# Sheet1.net
KiCad netlist of a schematic drawn in Altium Designer
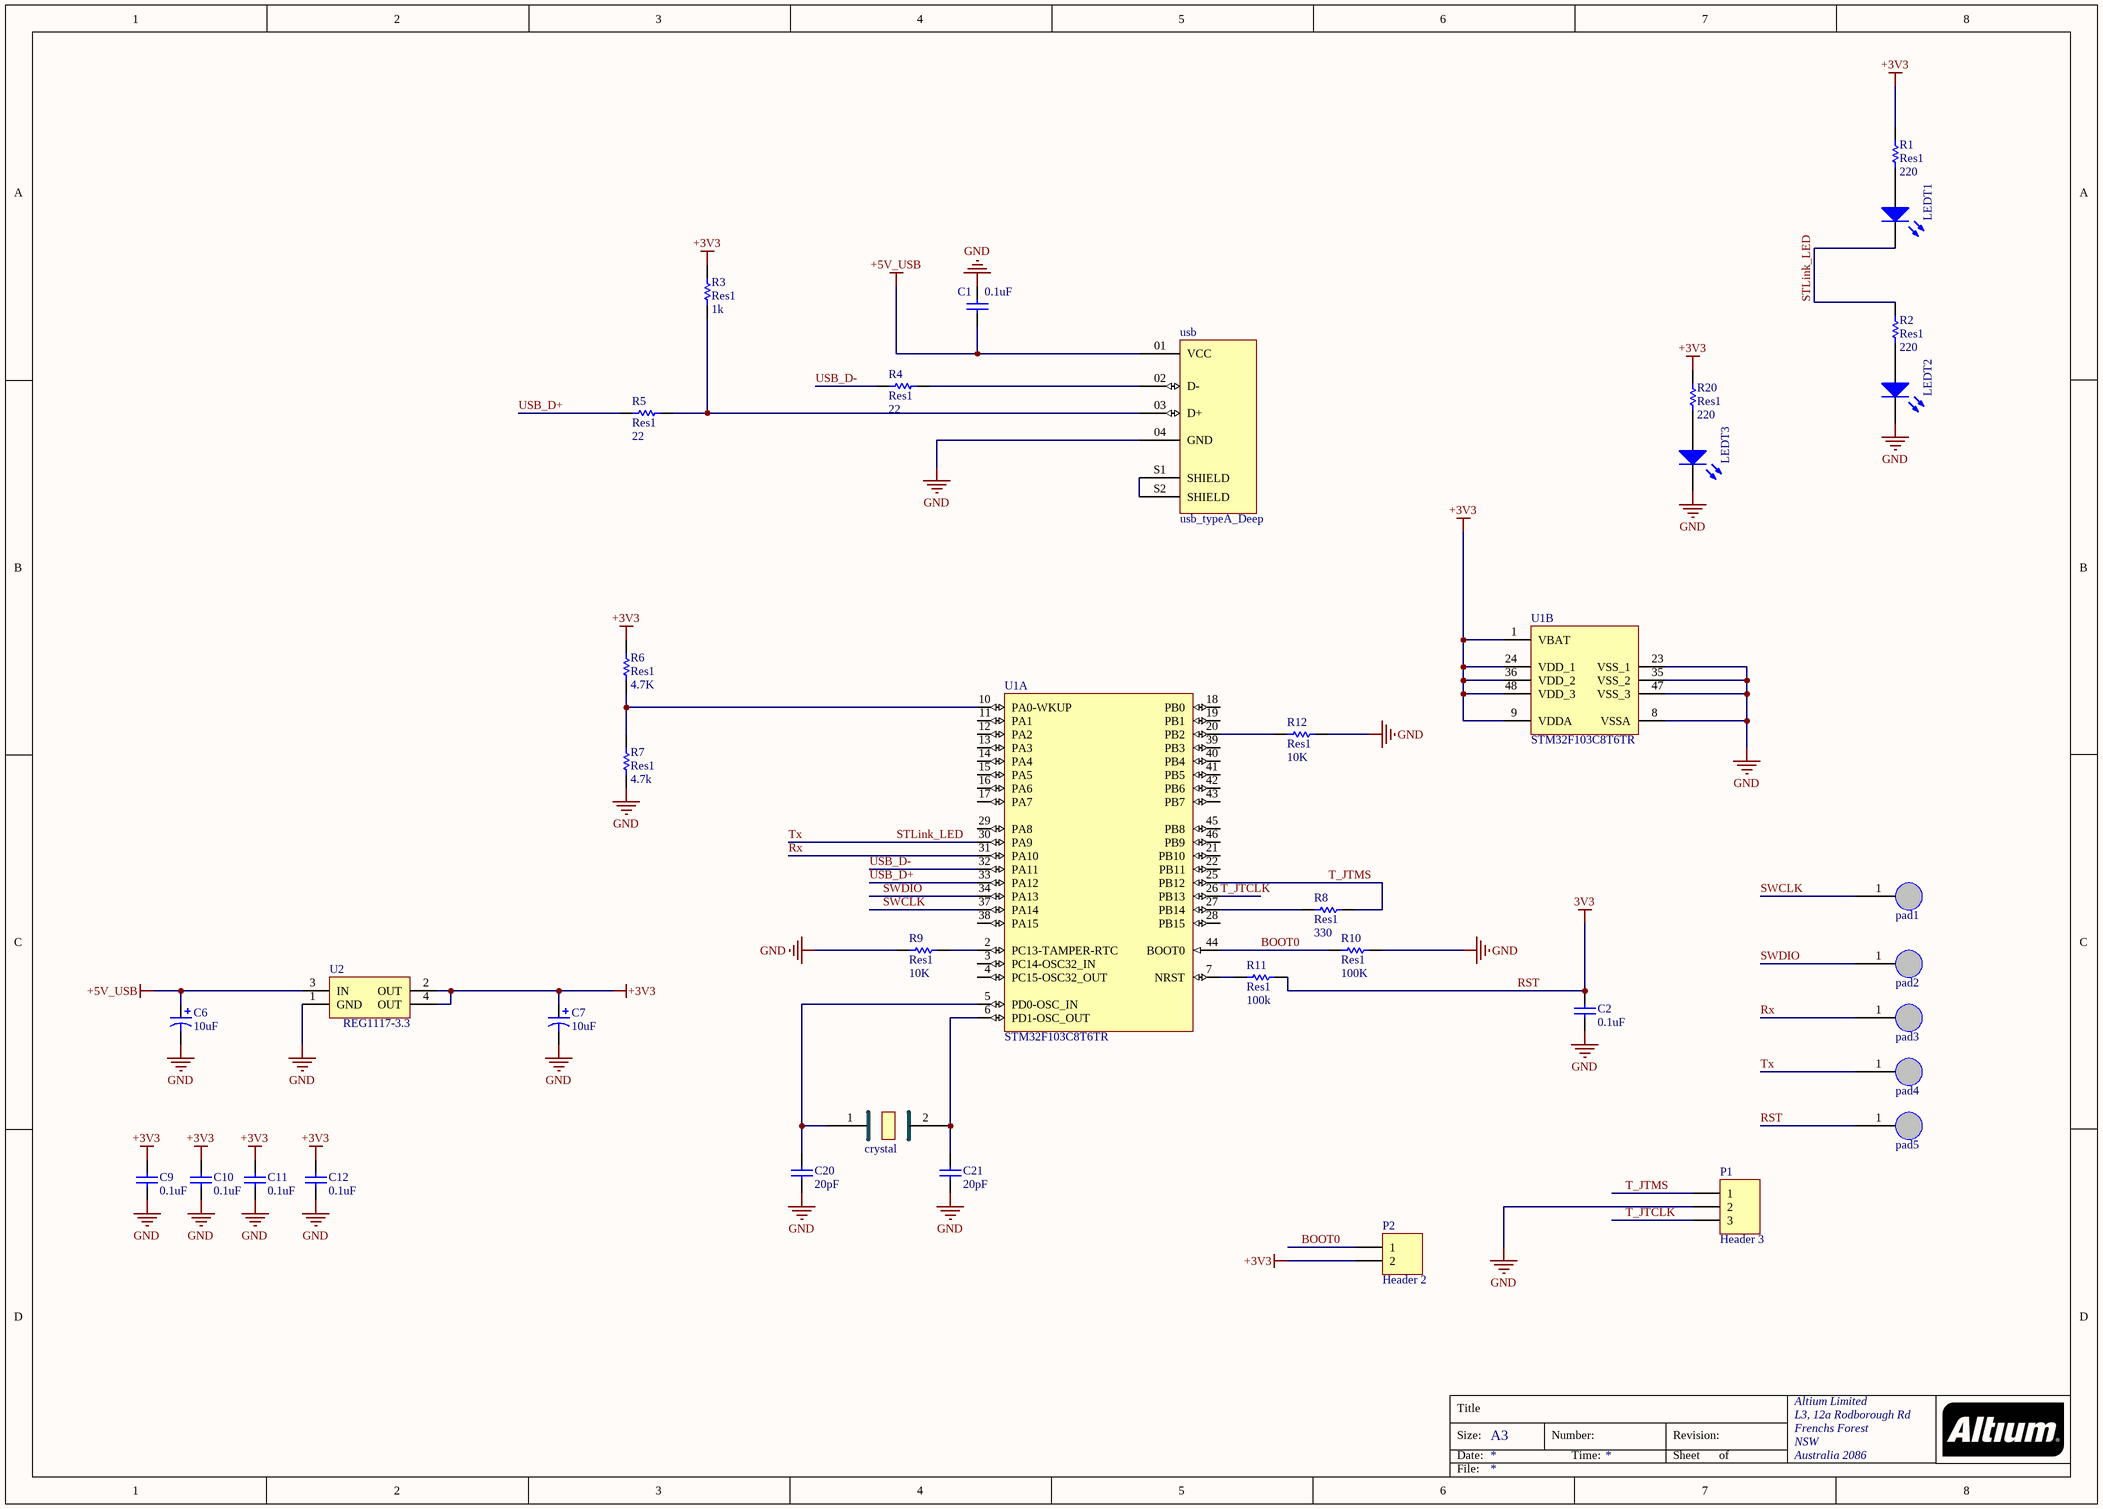
[diagram p0: Sheet1.SchDoc]

(export (version "E")
  (design (tool "Eeschema 10.0.6"))
  (components
    (comp (ref "C1")
      (value "0.1uF")
      (footprint "J1-0603")
      (description "Ceramic Chip Capacitor - Standard")
      (fields (field (name "Comment") "C0603") (field (name "PUBLISHER") "Altium Limited"))
      (libsource (lib "KEMET Chip Capacitor") (part "C0603"))
    )
    (comp (ref "C2")
      (value "0.1uF")
      (footprint "J1-0603")
      (description "Ceramic Chip Capacitor - Standard")
      (fields (field (name "Comment") "C0603") (field (name "PUBLISHER") "Altium Limited"))
      (libsource (lib "KEMET Chip Capacitor") (part "C0603"))
    )
    (comp (ref "C6")
      (value "10uF")
      (footprint "J1-0603")
      (fields (field (name "PUBLISHER") "Altium Limited"))
      (libsource (lib "Vishay Sprague Tantalum Chip Capacitor") (part "194D105X0015B2"))
    )
    (comp (ref "C7")
      (value "10uF")
      (footprint "J1-0603")
      (fields (field (name "PUBLISHER") "Altium Limited"))
      (libsource (lib "Vishay Sprague Tantalum Chip Capacitor") (part "194D105X0015B2"))
    )
    (comp (ref "C9")
      (value "0.1uF")
      (footprint "J1-0603")
      (description "Ceramic Chip Capacitor - Standard")
      (fields (field (name "Comment") "C0603") (field (name "PUBLISHER") "Altium Limited"))
      (libsource (lib "KEMET Chip Capacitor") (part "C0603"))
    )
    (comp (ref "C10")
      (value "0.1uF")
      (footprint "J1-0603")
      (description "Ceramic Chip Capacitor - Standard")
      (fields (field (name "Comment") "C0603") (field (name "PUBLISHER") "Altium Limited"))
      (libsource (lib "KEMET Chip Capacitor") (part "C0603"))
    )
    (comp (ref "C11")
      (value "0.1uF")
      (footprint "J1-0603")
      (description "Ceramic Chip Capacitor - Standard")
      (fields (field (name "Comment") "C0603") (field (name "PUBLISHER") "Altium Limited"))
      (libsource (lib "KEMET Chip Capacitor") (part "C0603"))
    )
    (comp (ref "C12")
      (value "0.1uF")
      (footprint "J1-0603")
      (description "Ceramic Chip Capacitor - Standard")
      (fields (field (name "Comment") "C0603") (field (name "PUBLISHER") "Altium Limited"))
      (libsource (lib "KEMET Chip Capacitor") (part "C0603"))
    )
    (comp (ref "C20")
      (value "20pF")
      (footprint "J1-0603")
      (description "Ceramic Chip Capacitor - Standard")
      (fields (field (name "Comment") "C0603") (field (name "PUBLISHER") "Altium Limited"))
      (libsource (lib "KEMET Chip Capacitor") (part "C0603"))
    )
    (comp (ref "C21")
      (value "20pF")
      (footprint "J1-0603")
      (description "Ceramic Chip Capacitor - Standard")
      (fields (field (name "Comment") "C0603") (field (name "PUBLISHER") "Altium Limited"))
      (libsource (lib "KEMET Chip Capacitor") (part "C0603"))
    )
    (comp (ref "crystal")
      (value "clockProducerDeep")
      (footprint "deep crystal")
      (libsource (lib "Schlib1") (part "deep crystal"))
    )
    (comp (ref "LEDT1")
      (value "~")
      (footprint "3518")
      (description "Typical BLUE SiC LED")
      (fields (field (name "PUBLISHER") "Altium Limited"))
      (libsource (lib "Miscellaneous Devices") (part "LED3"))
    )
    (comp (ref "LEDT2")
      (value "~")
      (footprint "3518")
      (description "Typical BLUE SiC LED")
      (fields (field (name "PUBLISHER") "Altium Limited"))
      (libsource (lib "Miscellaneous Devices") (part "LED3"))
    )
    (comp (ref "LEDT3")
      (value "~")
      (footprint "3518")
      (description "Typical BLUE SiC LED")
      (fields (field (name "PUBLISHER") "Altium Limited"))
      (libsource (lib "Miscellaneous Devices") (part "LED3"))
    )
    (comp (ref "P1")
      (value "Header 3")
      (footprint "HDR1X3")
      (description "Header, 3-Pin")
      (fields (field (name "PUBLISHER") "Altium Limited"))
      (libsource (lib "Miscellaneous Connectors") (part "Header 3"))
    )
    (comp (ref "P2")
      (value "Header 2")
      (footprint "HDR1X2")
      (description "Header, 2-Pin")
      (fields (field (name "PUBLISHER") "Altium Limited"))
      (libsource (lib "Miscellaneous Connectors") (part "Header 2"))
    )
    (comp (ref "pad1")
      (value "pad")
      (footprint "pad!")
      (description "test pad")
      (libsource (lib "Schlib1") (part "pad!"))
    )
    (comp (ref "pad2")
      (value "pad")
      (footprint "pad!")
      (description "test pad")
      (libsource (lib "Schlib1") (part "pad!"))
    )
    (comp (ref "pad3")
      (value "pad")
      (footprint "pad!")
      (description "test pad")
      (libsource (lib "Schlib1") (part "pad!"))
    )
    (comp (ref "pad4")
      (value "pad")
      (footprint "pad!")
      (description "test pad")
      (libsource (lib "Schlib1") (part "pad!"))
    )
    (comp (ref "pad5")
      (value "pad")
      (footprint "pad!")
      (description "test pad")
      (libsource (lib "Schlib1") (part "pad!"))
    )
    (comp (ref "R1")
      (value "Res1")
      (footprint "j1-0603")
      (description "Resistor")
      (fields (field (name "ALTIUM_VALUE") "220") (field (name "PUBLISHER") "Altium Limited"))
      (libsource (lib "Miscellaneous Devices") (part "Res1"))
    )
    (comp (ref "R2")
      (value "Res1")
      (footprint "j1-0603")
      (description "Resistor")
      (fields (field (name "ALTIUM_VALUE") "220") (field (name "PUBLISHER") "Altium Limited"))
      (libsource (lib "Miscellaneous Devices") (part "Res1"))
    )
    (comp (ref "R3")
      (value "Res1")
      (footprint "J1-0603")
      (description "Resistor")
      (fields (field (name "ALTIUM_VALUE") "1k") (field (name "PUBLISHER") "Altium Limited"))
      (libsource (lib "Miscellaneous Devices") (part "Res1"))
    )
    (comp (ref "R4")
      (value "Res1")
      (footprint "J1-0603")
      (description "Resistor")
      (fields (field (name "ALTIUM_VALUE") "22") (field (name "PUBLISHER") "Altium Limited"))
      (libsource (lib "Miscellaneous Devices") (part "Res1"))
    )
    (comp (ref "R5")
      (value "Res1")
      (footprint "J1-0603")
      (description "Resistor")
      (fields (field (name "ALTIUM_VALUE") "22") (field (name "PUBLISHER") "Altium Limited"))
      (libsource (lib "Miscellaneous Devices") (part "Res1"))
    )
    (comp (ref "R6")
      (value "Res1")
      (footprint "J1-0603")
      (description "Resistor")
      (fields (field (name "ALTIUM_VALUE") "4.7K") (field (name "PUBLISHER") "Altium Limited"))
      (libsource (lib "Miscellaneous Devices") (part "Res1"))
    )
    (comp (ref "R7")
      (value "Res1")
      (footprint "J1-0603")
      (description "Resistor")
      (fields (field (name "ALTIUM_VALUE") "4.7k") (field (name "PUBLISHER") "Altium Limited"))
      (libsource (lib "Miscellaneous Devices") (part "Res1"))
    )
    (comp (ref "R8")
      (value "Res1")
      (footprint "J1-0603")
      (description "Resistor")
      (fields (field (name "ALTIUM_VALUE") "330") (field (name "PUBLISHER") "Altium Limited"))
      (libsource (lib "Miscellaneous Devices") (part "Res1"))
    )
    (comp (ref "R9")
      (value "Res1")
      (footprint "J1-0603")
      (description "Resistor")
      (fields (field (name "ALTIUM_VALUE") "10K") (field (name "PUBLISHER") "Altium Limited"))
      (libsource (lib "Miscellaneous Devices") (part "Res1"))
    )
    (comp (ref "R10")
      (value "Res1")
      (footprint "J1-0603")
      (description "Resistor")
      (fields (field (name "ALTIUM_VALUE") "100K") (field (name "PUBLISHER") "Altium Limited"))
      (libsource (lib "Miscellaneous Devices") (part "Res1"))
    )
    (comp (ref "R11")
      (value "Res1")
      (footprint "J1-0603")
      (description "Resistor")
      (fields (field (name "ALTIUM_VALUE") "100k") (field (name "PUBLISHER") "Altium Limited"))
      (libsource (lib "Miscellaneous Devices") (part "Res1"))
    )
    (comp (ref "R12")
      (value "Res1")
      (footprint "J1-0603")
      (description "Resistor")
      (fields (field (name "ALTIUM_VALUE") "10K") (field (name "PUBLISHER") "Altium Limited"))
      (libsource (lib "Miscellaneous Devices") (part "Res1"))
    )
    (comp (ref "R20")
      (value "Res1")
      (footprint "j1-0603")
      (description "Resistor")
      (fields (field (name "ALTIUM_VALUE") "220") (field (name "PUBLISHER") "Altium Limited"))
      (libsource (lib "Miscellaneous Devices") (part "Res1"))
    )
    (comp (ref "U1")
      (value "STM32F103C8T6TR")
      (footprint "STM-LQFP48_L")
      (libsource (lib "STMicroelectronics STM32 F1") (part "STM32F103C8T6TR"))
    )
    (comp (ref "U2")
      (value "REG1117-3.3")
      (footprint "SOT223")
      (description "800mA and 1A Low Dropout Positive Regulator 2.85V, 3.3V, 5V, and Adjustable")
      (fields (field (name "PUBLISHER") "Altium Limited"))
      (libsource (lib "BB Power Mgt Voltage Regulator") (part "REG1117-3.3"))
    )
    (comp (ref "usb")
      (value "usb_typeA_Deep")
      (footprint "usb_typeA_Deep")
      (libsource (lib "Schlib1") (part "usb_typeA_Deep"))
    )
  )
  (nets
    (net (code "1") (name "+3V3") (class "Default")
      (node (ref "C10") (pin "2") (pinfunction "2_2") (pintype "passive"))
      (node (ref "C11") (pin "2") (pinfunction "2_2") (pintype "passive"))
      (node (ref "C12") (pin "2") (pinfunction "2_2") (pintype "passive"))
      (node (ref "C7") (pin "1") (pinfunction "1_1") (pintype "passive"))
      (node (ref "C9") (pin "2") (pinfunction "2_2") (pintype "passive"))
      (node (ref "P2") (pin "2") (pinfunction "2_2") (pintype "passive"))
      (node (ref "R1") (pin "1") (pinfunction "1_1") (pintype "passive"))
      (node (ref "R20") (pin "1") (pinfunction "1_1") (pintype "passive"))
      (node (ref "R3") (pin "2") (pinfunction "2_2") (pintype "passive"))
      (node (ref "R6") (pin "2") (pinfunction "2_2") (pintype "passive"))
      (node (ref "U1") (pin "1") (pinfunction "VBAT_1") (pintype "power_in"))
      (node (ref "U1") (pin "24") (pinfunction "VDD_1_24") (pintype "power_in"))
      (node (ref "U1") (pin "36") (pinfunction "VDD_2_36") (pintype "power_in"))
      (node (ref "U1") (pin "48") (pinfunction "VDD_3_48") (pintype "power_in"))
      (node (ref "U1") (pin "9") (pinfunction "VDDA_9") (pintype "power_in"))
      (node (ref "U2") (pin "2") (pinfunction "OUT_2") (pintype "power_in"))
      (node (ref "U2") (pin "4") (pinfunction "OUT_4") (pintype "power_in"))
    )
    (net (code "2") (name "+5V_USB") (class "Default")
      (node (ref "C1") (pin "1") (pinfunction "1_1") (pintype "passive"))
      (node (ref "C6") (pin "1") (pinfunction "1_1") (pintype "passive"))
      (node (ref "U2") (pin "3") (pinfunction "IN_3") (pintype "power_in"))
      (node (ref "usb") (pin "01") (pinfunction "VCC_01") (pintype "passive"))
    )
    (net (code "3") (name "/BOOT0") (class "Default")
      (node (ref "P2") (pin "1") (pinfunction "1_1") (pintype "passive"))
      (node (ref "R10") (pin "1") (pinfunction "1_1") (pintype "passive"))
      (node (ref "U1") (pin "44") (pinfunction "BOOT0_44") (pintype "input"))
    )
    (net (code "4") (name "/Rx") (class "Default")
      (node (ref "U1") (pin "31") (pinfunction "PA10_31") (pintype "bidirectional"))
      (node (ref "pad3") (pin "1") (pinfunction "1_1") (pintype "passive"))
    )
    (net (code "5") (name "/STLink_LED") (class "Default")
      (node (ref "LEDT1") (pin "2") (pinfunction "K_2") (pintype "passive"))
      (node (ref "R2") (pin "1") (pinfunction "1_1") (pintype "passive"))
      (node (ref "U1") (pin "30") (pinfunction "PA9_30") (pintype "bidirectional"))
      (node (ref "pad4") (pin "1") (pinfunction "1_1") (pintype "passive"))
    )
    (net (code "6") (name "/SWCLK") (class "Default")
      (node (ref "U1") (pin "37") (pinfunction "PA14_37") (pintype "bidirectional"))
      (node (ref "pad1") (pin "1") (pinfunction "1_1") (pintype "passive"))
    )
    (net (code "7") (name "/SWDIO") (class "Default")
      (node (ref "U1") (pin "34") (pinfunction "PA13_34") (pintype "bidirectional"))
      (node (ref "pad2") (pin "1") (pinfunction "1_1") (pintype "passive"))
    )
    (net (code "8") (name "/T_JTCLK") (class "Default")
      (node (ref "P1") (pin "3") (pinfunction "3_3") (pintype "passive"))
      (node (ref "U1") (pin "26") (pinfunction "PB13_26") (pintype "bidirectional"))
    )
    (net (code "9") (name "/T_JTMS") (class "Default")
      (node (ref "P1") (pin "1") (pinfunction "1_1") (pintype "passive"))
      (node (ref "R8") (pin "2") (pinfunction "2_2") (pintype "passive"))
      (node (ref "U1") (pin "25") (pinfunction "PB12_25") (pintype "bidirectional"))
    )
    (net (code "10") (name "/USB_D+") (class "Default")
      (node (ref "R5") (pin "2") (pinfunction "2_2") (pintype "passive"))
      (node (ref "U1") (pin "33") (pinfunction "PA12_33") (pintype "bidirectional"))
    )
    (net (code "11") (name "/USB_D-") (class "Default")
      (node (ref "R4") (pin "2") (pinfunction "2_2") (pintype "passive"))
      (node (ref "U1") (pin "32") (pinfunction "PA11_32") (pintype "bidirectional"))
    )
    (net (code "12") (name "3V3") (class "Default")
      (node (ref "C2") (pin "2") (pinfunction "2_2") (pintype "passive"))
      (node (ref "R11") (pin "2") (pinfunction "2_2") (pintype "passive"))
      (node (ref "pad5") (pin "1") (pinfunction "1_1") (pintype "passive"))
    )
    (net (code "13") (name "GND") (class "Default")
      (node (ref "C1") (pin "2") (pinfunction "2_2") (pintype "passive"))
      (node (ref "C10") (pin "1") (pinfunction "1_1") (pintype "passive"))
      (node (ref "C11") (pin "1") (pinfunction "1_1") (pintype "passive"))
      (node (ref "C12") (pin "1") (pinfunction "1_1") (pintype "passive"))
      (node (ref "C2") (pin "1") (pinfunction "1_1") (pintype "passive"))
      (node (ref "C20") (pin "1") (pinfunction "1_1") (pintype "passive"))
      (node (ref "C21") (pin "1") (pinfunction "1_1") (pintype "passive"))
      (node (ref "C6") (pin "2") (pinfunction "2_2") (pintype "passive"))
      (node (ref "C7") (pin "2") (pinfunction "2_2") (pintype "passive"))
      (node (ref "C9") (pin "1") (pinfunction "1_1") (pintype "passive"))
      (node (ref "LEDT2") (pin "2") (pinfunction "K_2") (pintype "passive"))
      (node (ref "LEDT3") (pin "2") (pinfunction "K_2") (pintype "passive"))
      (node (ref "P1") (pin "2") (pinfunction "2_2") (pintype "passive"))
      (node (ref "R10") (pin "2") (pinfunction "2_2") (pintype "passive"))
      (node (ref "R12") (pin "2") (pinfunction "2_2") (pintype "passive"))
      (node (ref "R7") (pin "1") (pinfunction "1_1") (pintype "passive"))
      (node (ref "R9") (pin "1") (pinfunction "1_1") (pintype "passive"))
      (node (ref "U1") (pin "23") (pinfunction "VSS_1_23") (pintype "power_in"))
      (node (ref "U1") (pin "35") (pinfunction "VSS_2_35") (pintype "power_in"))
      (node (ref "U1") (pin "47") (pinfunction "VSS_3_47") (pintype "power_in"))
      (node (ref "U1") (pin "8") (pinfunction "VSSA_8") (pintype "power_in"))
      (node (ref "U2") (pin "1") (pinfunction "GND_1") (pintype "power_in"))
      (node (ref "usb") (pin "04") (pinfunction "GND_04") (pintype "passive"))
    )
    (net (code "14") (name "Net-(LEDT1-A)") (class "Default")
      (node (ref "LEDT1") (pin "1") (pinfunction "A_1") (pintype "passive"))
      (node (ref "R1") (pin "2") (pinfunction "2_2") (pintype "passive"))
    )
    (net (code "15") (name "Net-(LEDT2-A)") (class "Default")
      (node (ref "LEDT2") (pin "1") (pinfunction "A_1") (pintype "passive"))
      (node (ref "R2") (pin "2") (pinfunction "2_2") (pintype "passive"))
    )
    (net (code "16") (name "Net-(LEDT3-A)") (class "Default")
      (node (ref "LEDT3") (pin "1") (pinfunction "A_1") (pintype "passive"))
      (node (ref "R20") (pin "2") (pinfunction "2_2") (pintype "passive"))
    )
    (net (code "17") (name "Net-(U1A-NRST)") (class "Default")
      (node (ref "R11") (pin "1") (pinfunction "1_1") (pintype "passive"))
      (node (ref "U1") (pin "7") (pinfunction "NRST_7") (pintype "bidirectional"))
    )
    (net (code "18") (name "Net-(U1A-PA0-WKUP)") (class "Default")
      (node (ref "R6") (pin "1") (pinfunction "1_1") (pintype "passive"))
      (node (ref "R7") (pin "2") (pinfunction "2_2") (pintype "passive"))
      (node (ref "U1") (pin "10") (pinfunction "PA0-WKUP_10") (pintype "bidirectional"))
    )
    (net (code "19") (name "Net-(U1A-PB2)") (class "Default")
      (node (ref "R12") (pin "1") (pinfunction "1_1") (pintype "passive"))
      (node (ref "U1") (pin "20") (pinfunction "PB2_20") (pintype "bidirectional"))
    )
    (net (code "20") (name "Net-(U1A-PB14)") (class "Default")
      (node (ref "R8") (pin "1") (pinfunction "1_1") (pintype "passive"))
      (node (ref "U1") (pin "27") (pinfunction "PB14_27") (pintype "bidirectional"))
    )
    (net (code "21") (name "Net-(U1A-PC13-TAMPER-RTC)") (class "Default")
      (node (ref "R9") (pin "2") (pinfunction "2_2") (pintype "passive"))
      (node (ref "U1") (pin "2") (pinfunction "PC13-TAMPER-RTC_2") (pintype "bidirectional"))
    )
    (net (code "22") (name "Net-(U1A-PD0-OSC_IN)") (class "Default")
      (node (ref "C20") (pin "2") (pinfunction "2_2") (pintype "passive"))
      (node (ref "U1") (pin "5") (pinfunction "PD0-OSC_IN_5") (pintype "bidirectional"))
      (node (ref "crystal") (pin "1") (pinfunction "1_1") (pintype "passive"))
    )
    (net (code "23") (name "Net-(U1A-PD1-OSC_OUT)") (class "Default")
      (node (ref "C21") (pin "2") (pinfunction "2_2") (pintype "passive"))
      (node (ref "U1") (pin "6") (pinfunction "PD1-OSC_OUT_6") (pintype "bidirectional"))
      (node (ref "crystal") (pin "2") (pinfunction "2_2") (pintype "passive"))
    )
    (net (code "24") (name "Net-(usb-D+)") (class "Default")
      (node (ref "R3") (pin "1") (pinfunction "1_1") (pintype "passive"))
      (node (ref "R5") (pin "1") (pinfunction "1_1") (pintype "passive"))
      (node (ref "usb") (pin "03") (pinfunction "D+_03") (pintype "bidirectional"))
    )
    (net (code "25") (name "Net-(usb-D-)") (class "Default")
      (node (ref "R4") (pin "1") (pinfunction "1_1") (pintype "passive"))
      (node (ref "usb") (pin "02") (pinfunction "D-_02") (pintype "bidirectional"))
    )
    (net (code "26") (name "Net-(usb-SHIELD-PadS1)") (class "Default")
      (node (ref "usb") (pin "S1") (pinfunction "SHIELD_S1") (pintype "passive"))
      (node (ref "usb") (pin "S2") (pinfunction "SHIELD_S2") (pintype "passive"))
    )
    (net (code "27") (name "unconnected-(U1A-PA1-Pad11)") (class "Default")
      (node (ref "U1") (pin "11") (pinfunction "PA1_11") (pintype "bidirectional"))
    )
    (net (code "28") (name "unconnected-(U1A-PA2-Pad12)") (class "Default")
      (node (ref "U1") (pin "12") (pinfunction "PA2_12") (pintype "bidirectional"))
    )
    (net (code "29") (name "unconnected-(U1A-PA3-Pad13)") (class "Default")
      (node (ref "U1") (pin "13") (pinfunction "PA3_13") (pintype "bidirectional"))
    )
    (net (code "30") (name "unconnected-(U1A-PA4-Pad14)") (class "Default")
      (node (ref "U1") (pin "14") (pinfunction "PA4_14") (pintype "bidirectional"))
    )
    (net (code "31") (name "unconnected-(U1A-PA5-Pad15)") (class "Default")
      (node (ref "U1") (pin "15") (pinfunction "PA5_15") (pintype "bidirectional"))
    )
    (net (code "32") (name "unconnected-(U1A-PA6-Pad16)") (class "Default")
      (node (ref "U1") (pin "16") (pinfunction "PA6_16") (pintype "bidirectional"))
    )
    (net (code "33") (name "unconnected-(U1A-PA7-Pad17)") (class "Default")
      (node (ref "U1") (pin "17") (pinfunction "PA7_17") (pintype "bidirectional"))
    )
    (net (code "34") (name "unconnected-(U1A-PA8-Pad29)") (class "Default")
      (node (ref "U1") (pin "29") (pinfunction "PA8_29") (pintype "bidirectional"))
    )
    (net (code "35") (name "unconnected-(U1A-PA15-Pad38)") (class "Default")
      (node (ref "U1") (pin "38") (pinfunction "PA15_38") (pintype "bidirectional"))
    )
    (net (code "36") (name "unconnected-(U1A-PB0-Pad18)") (class "Default")
      (node (ref "U1") (pin "18") (pinfunction "PB0_18") (pintype "bidirectional"))
    )
    (net (code "37") (name "unconnected-(U1A-PB1-Pad19)") (class "Default")
      (node (ref "U1") (pin "19") (pinfunction "PB1_19") (pintype "bidirectional"))
    )
    (net (code "38") (name "unconnected-(U1A-PB3-Pad39)") (class "Default")
      (node (ref "U1") (pin "39") (pinfunction "PB3_39") (pintype "bidirectional"))
    )
    (net (code "39") (name "unconnected-(U1A-PB4-Pad40)") (class "Default")
      (node (ref "U1") (pin "40") (pinfunction "PB4_40") (pintype "bidirectional"))
    )
    (net (code "40") (name "unconnected-(U1A-PB5-Pad41)") (class "Default")
      (node (ref "U1") (pin "41") (pinfunction "PB5_41") (pintype "bidirectional"))
    )
    (net (code "41") (name "unconnected-(U1A-PB6-Pad42)") (class "Default")
      (node (ref "U1") (pin "42") (pinfunction "PB6_42") (pintype "bidirectional"))
    )
    (net (code "42") (name "unconnected-(U1A-PB7-Pad43)") (class "Default")
      (node (ref "U1") (pin "43") (pinfunction "PB7_43") (pintype "bidirectional"))
    )
    (net (code "43") (name "unconnected-(U1A-PB8-Pad45)") (class "Default")
      (node (ref "U1") (pin "45") (pinfunction "PB8_45") (pintype "bidirectional"))
    )
    (net (code "44") (name "unconnected-(U1A-PB9-Pad46)") (class "Default")
      (node (ref "U1") (pin "46") (pinfunction "PB9_46") (pintype "bidirectional"))
    )
    (net (code "45") (name "unconnected-(U1A-PB10-Pad21)") (class "Default")
      (node (ref "U1") (pin "21") (pinfunction "PB10_21") (pintype "bidirectional"))
    )
    (net (code "46") (name "unconnected-(U1A-PB11-Pad22)") (class "Default")
      (node (ref "U1") (pin "22") (pinfunction "PB11_22") (pintype "bidirectional"))
    )
    (net (code "47") (name "unconnected-(U1A-PB15-Pad28)") (class "Default")
      (node (ref "U1") (pin "28") (pinfunction "PB15_28") (pintype "bidirectional"))
    )
    (net (code "48") (name "unconnected-(U1A-PC14-OSC32_IN-Pad3)") (class "Default")
      (node (ref "U1") (pin "3") (pinfunction "PC14-OSC32_IN_3") (pintype "bidirectional"))
    )
    (net (code "49") (name "unconnected-(U1A-PC15-OSC32_OUT-Pad4)") (class "Default")
      (node (ref "U1") (pin "4") (pinfunction "PC15-OSC32_OUT_4") (pintype "bidirectional"))
    )
  )
)
